# Netzteil.net
KiCad netlist of a schematic drawn in EAGLE
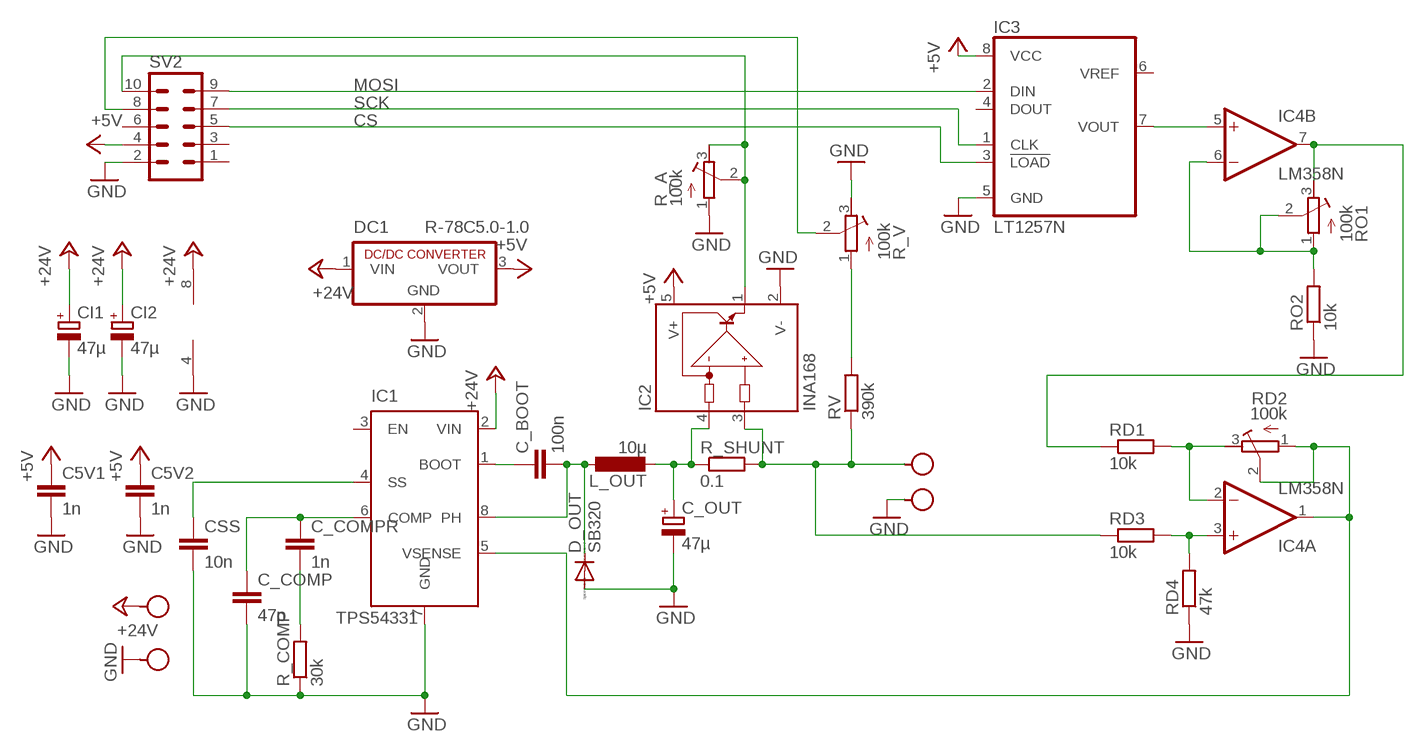
[diagram p0: schematic, sheet 1]

(export (version "E")
  (design (tool "Eeschema 10.0.6"))
  (components
    (comp (ref "C5V1")
      (value "1n")
      (footprint "eagle-import:C025-025X050")
      (libsource (lib "eagle-import") (part "C-EU025-025X050"))
    )
    (comp (ref "C5V2")
      (value "1n")
      (footprint "eagle-import:C025-025X050")
      (libsource (lib "eagle-import") (part "C-EU025-025X050"))
    )
    (comp (ref "CI1")
      (value "47µ")
      (footprint "eagle-import:E2,5-6")
      (libsource (lib "eagle-import") (part "CPOL-EUE2.5-6"))
    )
    (comp (ref "CI2")
      (value "47µ")
      (footprint "eagle-import:E2,5-6")
      (libsource (lib "eagle-import") (part "CPOL-EUE2.5-6"))
    )
    (comp (ref "CSS")
      (value "10n")
      (footprint "eagle-import:C025-025X050")
      (libsource (lib "eagle-import") (part "C-EU025-025X050"))
    )
    (comp (ref "C_BOOT")
      (value "100n")
      (footprint "eagle-import:C025-025X050")
      (libsource (lib "eagle-import") (part "C-EU025-025X050"))
    )
    (comp (ref "C_COMP")
      (value "47p")
      (footprint "eagle-import:C025-025X050")
      (libsource (lib "eagle-import") (part "C-EU025-025X050"))
    )
    (comp (ref "C_COMPR")
      (value "1n")
      (footprint "eagle-import:C025-025X050")
      (libsource (lib "eagle-import") (part "C-EU025-025X050"))
    )
    (comp (ref "C_OUT")
      (value "47µ")
      (footprint "eagle-import:E2,5-6")
      (libsource (lib "eagle-import") (part "CPOL-EUE2.5-6"))
    )
    (comp (ref "DC1")
      (value "R-78C5.0-1.0")
      (footprint "eagle-import:SIP3")
      (fields (field (name "MF") "RECOM POWER"))
      (libsource (lib "eagle-import") (part "R-78C-1.05.0"))
    )
    (comp (ref "D_OUT")
      (value "SB320")
      (footprint "eagle-import:DO201-15")
      (libsource (lib "eagle-import") (part "SB320"))
    )
    (comp (ref "H1")
      (value "SEW_HOLE-SMALL")
      (footprint "eagle-import:SIMPLE_HOLE_SM")
      (libsource (lib "eagle-import") (part "SEW_HOLE-SMALL"))
    )
    (comp (ref "H2")
      (value "SEW_HOLE-SMALL")
      (footprint "eagle-import:SIMPLE_HOLE_SM")
      (libsource (lib "eagle-import") (part "SEW_HOLE-SMALL"))
    )
    (comp (ref "H3")
      (value "SEW_HOLE-SMALL")
      (footprint "eagle-import:SIMPLE_HOLE_SM")
      (libsource (lib "eagle-import") (part "SEW_HOLE-SMALL"))
    )
    (comp (ref "H4")
      (value "SEW_HOLE-SMALL")
      (footprint "eagle-import:SIMPLE_HOLE_SM")
      (libsource (lib "eagle-import") (part "SEW_HOLE-SMALL"))
    )
    (comp (ref "IC1")
      (value "TPS54331")
      (footprint "eagle-import:D_R-PDSO-G08")
      (fields
        (field (name "MPN") "TPS5410DR")
        (field (name "MF") "TEXAS INSTRUMENTS")
        (field (name "MPN_1") "TPS5410DG4")
      )
      (libsource (lib "eagle-import") (part "TPS5410"))
    )
    (comp (ref "IC2")
      (value "INA168")
      (footprint "eagle-import:SOT23-5")
      (fields (field (name "MF") "TEXAS INSTRUMENTS") (field (name "MPN") "INA168NA/250"))
      (libsource (lib "eagle-import") (part "INA168"))
    )
    (comp (ref "IC3")
      (value "LT1257N")
      (footprint "eagle-import:DIL08")
      (libsource (lib "eagle-import") (part "LT1257N"))
    )
    (comp (ref "IC4")
      (value "LM358N")
      (footprint "eagle-import:DIL08")
      (libsource (lib "eagle-import") (part "LM358N"))
    )
    (comp (ref "L_OUT")
      (value "10µ")
      (footprint "eagle-import:PIS2816")
      (libsource (lib "eagle-import") (part "L-EUPIS2816"))
    )
    (comp (ref "RD1")
      (value "10k")
      (footprint "eagle-import:0309_12")
      (libsource (lib "eagle-import") (part "R-EU_0309/12"))
    )
    (comp (ref "RD2")
      (value "100k")
      (footprint "eagle-import:RTRIM64Y")
      (libsource (lib "eagle-import") (part "R-TRIMM64Y"))
    )
    (comp (ref "RD3")
      (value "10k")
      (footprint "eagle-import:0309_12")
      (libsource (lib "eagle-import") (part "R-EU_0309/12"))
    )
    (comp (ref "RD4")
      (value "47k")
      (footprint "eagle-import:0309_12")
      (libsource (lib "eagle-import") (part "R-EU_0309/12"))
    )
    (comp (ref "RO1")
      (value "100k")
      (footprint "eagle-import:RTRIM64Y")
      (libsource (lib "eagle-import") (part "R-TRIMM64Y"))
    )
    (comp (ref "RO2")
      (value "10k")
      (footprint "eagle-import:0309_12")
      (libsource (lib "eagle-import") (part "R-EU_0309/12"))
    )
    (comp (ref "RV")
      (value "390k")
      (footprint "eagle-import:0309_12")
      (libsource (lib "eagle-import") (part "R-EU_0309/12"))
    )
    (comp (ref "R_A")
      (value "100k")
      (footprint "eagle-import:RTRIM64Y")
      (libsource (lib "eagle-import") (part "R-TRIMM64Y"))
    )
    (comp (ref "R_COMP")
      (value "30k")
      (footprint "eagle-import:0309_12")
      (libsource (lib "eagle-import") (part "R-EU_0309/12"))
    )
    (comp (ref "R_SHUNT")
      (value "0.1")
      (footprint "eagle-import:P0817_22")
      (libsource (lib "eagle-import") (part "R-EU_0817/22"))
    )
    (comp (ref "R_V")
      (value "100k")
      (footprint "eagle-import:RTRIM64Y")
      (libsource (lib "eagle-import") (part "R-TRIMM64Y"))
    )
    (comp (ref "SV2")
      (value "ML10")
      (footprint "eagle-import:ML10")
      (libsource (lib "eagle-import") (part "ML10"))
    )
  )
  (nets
    (net (code "1") (name "+5V") (class "Default")
      (node (ref "C5V1") (pin "1") (pinfunction "1_1") (pintype "passive"))
      (node (ref "C5V2") (pin "1") (pinfunction "1_1") (pintype "passive"))
      (node (ref "DC1") (pin "3") (pinfunction "VOUT_3") (pintype "passive"))
      (node (ref "IC2") (pin "5") (pinfunction "V+_5") (pintype "power_in"))
      (node (ref "IC3") (pin "8") (pinfunction "VCC_8") (pintype "power_in"))
      (node (ref "SV2") (pin "4") (pinfunction "4_4") (pintype "passive"))
    )
    (net (code "2") (name "+24V") (class "Default")
      (node (ref "CI1") (pin "+") (pinfunction "+_+") (pintype "passive"))
      (node (ref "CI2") (pin "+") (pinfunction "+_+") (pintype "passive"))
      (node (ref "DC1") (pin "1") (pinfunction "VIN_1") (pintype "passive"))
      (node (ref "H3") (pin "P$1") (pinfunction "P$1_P$1") (pintype "bidirectional"))
      (node (ref "IC1") (pin "2") (pinfunction "VIN_2") (pintype "input"))
      (node (ref "IC4") (pin "8") (pinfunction "V+_8") (pintype "power_in"))
    )
    (net (code "3") (name "/CS") (class "Default")
      (node (ref "IC3") (pin "3") (pinfunction "~{LOAD}_3") (pintype "input"))
      (node (ref "SV2") (pin "5") (pinfunction "5_5") (pintype "passive"))
    )
    (net (code "4") (name "/MOSI") (class "Default")
      (node (ref "IC3") (pin "2") (pinfunction "DIN_2") (pintype "input"))
      (node (ref "SV2") (pin "9") (pinfunction "9_9") (pintype "passive"))
    )
    (net (code "5") (name "/SCK") (class "Default")
      (node (ref "IC3") (pin "1") (pinfunction "CLK_1") (pintype "input"))
      (node (ref "SV2") (pin "7") (pinfunction "7_7") (pintype "passive"))
    )
    (net (code "6") (name "GND") (class "Default")
      (node (ref "C5V1") (pin "2") (pinfunction "2_2") (pintype "passive"))
      (node (ref "C5V2") (pin "2") (pinfunction "2_2") (pintype "passive"))
      (node (ref "CI1") (pin "-") (pinfunction "-_-") (pintype "passive"))
      (node (ref "CI2") (pin "-") (pinfunction "-_-") (pintype "passive"))
      (node (ref "CSS") (pin "2") (pinfunction "2_2") (pintype "passive"))
      (node (ref "C_COMP") (pin "2") (pinfunction "2_2") (pintype "passive"))
      (node (ref "C_OUT") (pin "-") (pinfunction "-_-") (pintype "passive"))
      (node (ref "DC1") (pin "2") (pinfunction "GND_2") (pintype "passive"))
      (node (ref "D_OUT") (pin "A") (pinfunction "A_A") (pintype "passive"))
      (node (ref "H2") (pin "P$1") (pinfunction "P$1_P$1") (pintype "bidirectional"))
      (node (ref "H4") (pin "P$1") (pinfunction "P$1_P$1") (pintype "bidirectional"))
      (node (ref "IC1") (pin "7") (pinfunction "GND_7") (pintype "input"))
      (node (ref "IC2") (pin "2") (pinfunction "V-_2") (pintype "power_in"))
      (node (ref "IC3") (pin "5") (pinfunction "GND_5") (pintype "power_in"))
      (node (ref "IC4") (pin "4") (pinfunction "V-_4") (pintype "power_in"))
      (node (ref "RD4") (pin "1") (pinfunction "1_1") (pintype "passive"))
      (node (ref "RO2") (pin "1") (pinfunction "1_1") (pintype "passive"))
      (node (ref "R_A") (pin "1") (pinfunction "E_1") (pintype "passive"))
      (node (ref "R_COMP") (pin "1") (pinfunction "1_1") (pintype "passive"))
      (node (ref "R_V") (pin "3") (pinfunction "A_3") (pintype "passive"))
      (node (ref "SV2") (pin "2") (pinfunction "2_2") (pintype "passive"))
    )
    (net (code "7") (name "Net-(C_COMPR-Pad2)") (class "Default")
      (node (ref "C_COMPR") (pin "2") (pinfunction "2_2") (pintype "passive"))
      (node (ref "R_COMP") (pin "2") (pinfunction "2_2") (pintype "passive"))
    )
    (net (code "8") (name "Net-(IC1-BOOT)") (class "Default")
      (node (ref "C_BOOT") (pin "1") (pinfunction "1_1") (pintype "passive"))
      (node (ref "IC1") (pin "1") (pinfunction "BOOT_1") (pintype "output"))
    )
    (net (code "9") (name "Net-(IC1-COMP)") (class "Default")
      (node (ref "C_COMP") (pin "1") (pinfunction "1_1") (pintype "passive"))
      (node (ref "C_COMPR") (pin "1") (pinfunction "1_1") (pintype "passive"))
      (node (ref "IC1") (pin "6") (pinfunction "COMP_6") (pintype "input"))
    )
    (net (code "10") (name "Net-(IC1-PH)") (class "Default")
      (node (ref "C_BOOT") (pin "2") (pinfunction "2_2") (pintype "passive"))
      (node (ref "D_OUT") (pin "C") (pinfunction "C_C") (pintype "passive"))
      (node (ref "IC1") (pin "8") (pinfunction "PH_8") (pintype "output"))
      (node (ref "L_OUT") (pin "1") (pinfunction "1_1") (pintype "passive"))
    )
    (net (code "11") (name "Net-(IC1-SS)") (class "Default")
      (node (ref "CSS") (pin "1") (pinfunction "1_1") (pintype "passive"))
      (node (ref "IC1") (pin "4") (pinfunction "SS_4") (pintype "input"))
    )
    (net (code "12") (name "Net-(IC1-VSENSE)") (class "Default")
      (node (ref "IC1") (pin "5") (pinfunction "VSENSE_5") (pintype "input"))
      (node (ref "IC4") (pin "1") (pinfunction "OUT_1") (pintype "output"))
      (node (ref "RD2") (pin "1") (pinfunction "E_1") (pintype "passive"))
      (node (ref "RD2") (pin "2") (pinfunction "S_2") (pintype "passive"))
    )
    (net (code "13") (name "Net-(IC2-IN+)") (class "Default")
      (node (ref "H1") (pin "P$1") (pinfunction "P$1_P$1") (pintype "bidirectional"))
      (node (ref "IC2") (pin "3") (pinfunction "IN+_3") (pintype "input"))
      (node (ref "RD3") (pin "1") (pinfunction "1_1") (pintype "passive"))
      (node (ref "RV") (pin "1") (pinfunction "1_1") (pintype "passive"))
      (node (ref "R_SHUNT") (pin "2") (pinfunction "2_2") (pintype "passive"))
    )
    (net (code "14") (name "Net-(IC2-IN-)") (class "Default")
      (node (ref "C_OUT") (pin "+") (pinfunction "+_+") (pintype "passive"))
      (node (ref "IC2") (pin "4") (pinfunction "IN-_4") (pintype "input"))
      (node (ref "L_OUT") (pin "2") (pinfunction "2_2") (pintype "passive"))
      (node (ref "R_SHUNT") (pin "1") (pinfunction "1_1") (pintype "passive"))
    )
    (net (code "15") (name "Net-(IC2-OUT)") (class "Default")
      (node (ref "IC2") (pin "1") (pinfunction "OUT_1") (pintype "output"))
      (node (ref "R_A") (pin "2") (pinfunction "S_2") (pintype "passive"))
      (node (ref "R_A") (pin "3") (pinfunction "A_3") (pintype "passive"))
      (node (ref "SV2") (pin "10") (pinfunction "10_10") (pintype "passive"))
    )
    (net (code "16") (name "Net-(IC3-VOUT)") (class "Default")
      (node (ref "IC3") (pin "7") (pinfunction "VOUT_7") (pintype "output"))
      (node (ref "IC4") (pin "5") (pinfunction "+IN_5") (pintype "input"))
    )
    (net (code "17") (name "Net-(IC4A-+IN)") (class "Default")
      (node (ref "IC4") (pin "3") (pinfunction "+IN_3") (pintype "input"))
      (node (ref "RD3") (pin "2") (pinfunction "2_2") (pintype "passive"))
      (node (ref "RD4") (pin "2") (pinfunction "2_2") (pintype "passive"))
    )
    (net (code "18") (name "Net-(IC4A--IN)") (class "Default")
      (node (ref "IC4") (pin "2") (pinfunction "-IN_2") (pintype "input"))
      (node (ref "RD1") (pin "2") (pinfunction "2_2") (pintype "passive"))
      (node (ref "RD2") (pin "3") (pinfunction "A_3") (pintype "passive"))
    )
    (net (code "19") (name "Net-(IC4B--IN)") (class "Default")
      (node (ref "IC4") (pin "6") (pinfunction "-IN_6") (pintype "input"))
      (node (ref "RO1") (pin "1") (pinfunction "E_1") (pintype "passive"))
      (node (ref "RO1") (pin "2") (pinfunction "S_2") (pintype "passive"))
      (node (ref "RO2") (pin "2") (pinfunction "2_2") (pintype "passive"))
    )
    (net (code "20") (name "Net-(IC4B-OUT)") (class "Default")
      (node (ref "IC4") (pin "7") (pinfunction "OUT_7") (pintype "output"))
      (node (ref "RD1") (pin "1") (pinfunction "1_1") (pintype "passive"))
      (node (ref "RO1") (pin "3") (pinfunction "A_3") (pintype "passive"))
    )
    (net (code "21") (name "Net-(R_V-E)") (class "Default")
      (node (ref "RV") (pin "2") (pinfunction "2_2") (pintype "passive"))
      (node (ref "R_V") (pin "1") (pinfunction "E_1") (pintype "passive"))
    )
    (net (code "22") (name "Net-(R_V-S)") (class "Default")
      (node (ref "R_V") (pin "2") (pinfunction "S_2") (pintype "passive"))
      (node (ref "SV2") (pin "8") (pinfunction "8_8") (pintype "passive"))
    )
    (net (code "23") (name "unconnected-(IC1-EN-Pad3)") (class "Default")
      (node (ref "IC1") (pin "3") (pinfunction "EN_3") (pintype "input"))
    )
    (net (code "24") (name "unconnected-(IC3-DOUT-Pad4)") (class "Default")
      (node (ref "IC3") (pin "4") (pinfunction "DOUT_4") (pintype "output"))
    )
    (net (code "25") (name "unconnected-(IC3-VREF-Pad6)") (class "Default")
      (node (ref "IC3") (pin "6") (pinfunction "VREF_6") (pintype "input"))
    )
    (net (code "26") (name "unconnected-(SV2-Pad1)") (class "Default")
      (node (ref "SV2") (pin "1") (pinfunction "1_1") (pintype "passive"))
    )
    (net (code "27") (name "unconnected-(SV2-Pad3)") (class "Default")
      (node (ref "SV2") (pin "3") (pinfunction "3_3") (pintype "passive"))
    )
    (net (code "28") (name "unconnected-(SV2-Pad6)") (class "Default")
      (node (ref "SV2") (pin "6") (pinfunction "6_6") (pintype "passive"))
    )
  )
)
